# TreeShield.net
KiCad netlist of a schematic drawn in EAGLE
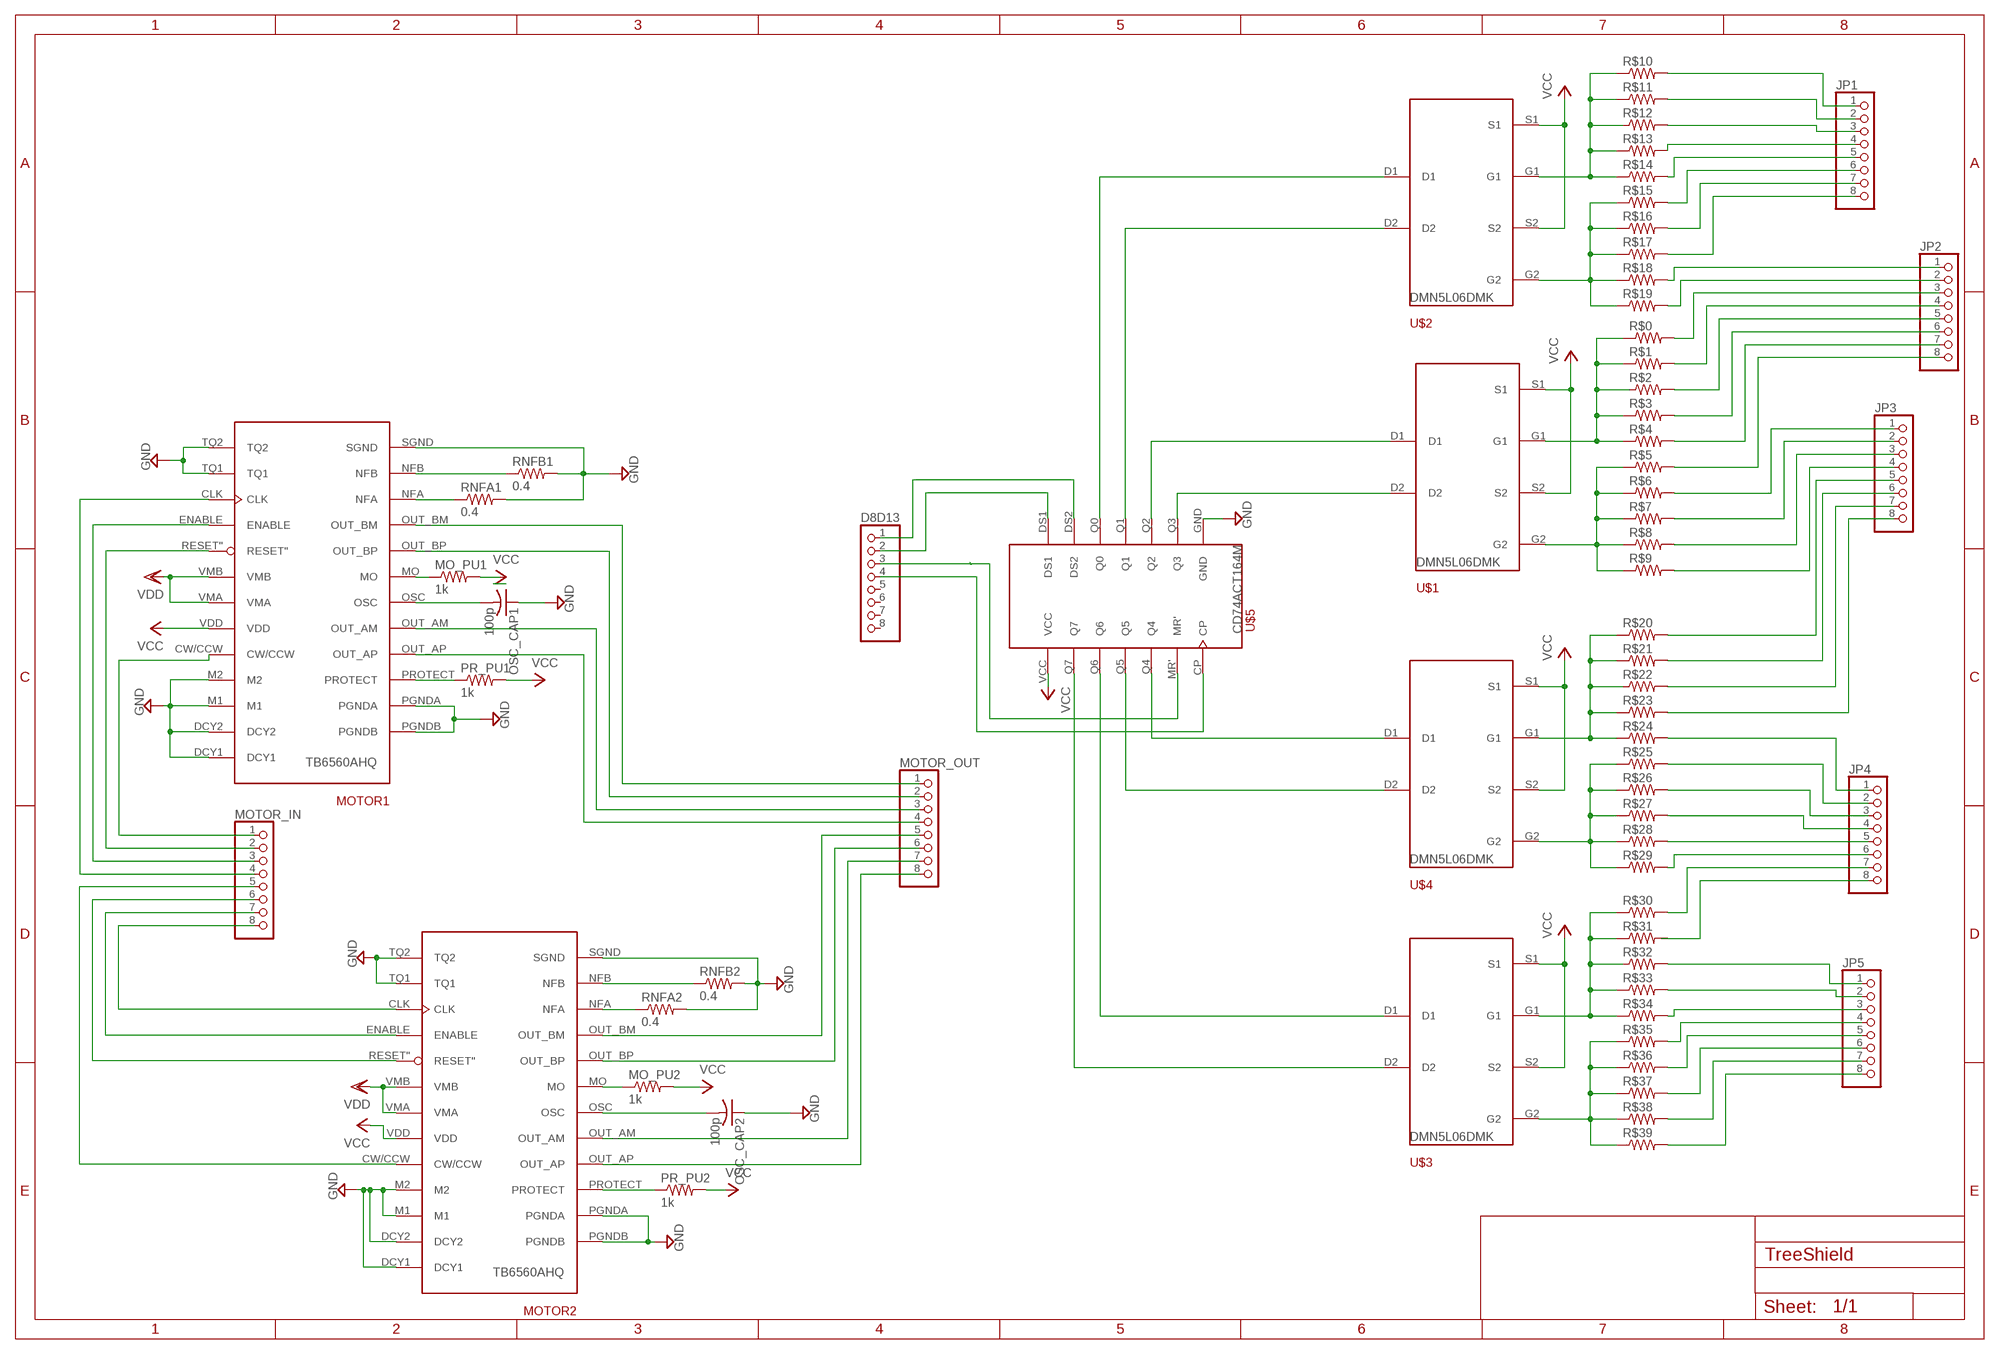
[diagram p0: schematic, sheet 1]

(export (version "E")
  (design (tool "Eeschema 10.0.6"))
  (components
    (comp (ref "D8D13")
      (value "PINHD-1X8CLEANBIG")
      (footprint "eagle-import:1X08-CLEANBIG")
      (libsource (lib "eagle-import") (part "PINHD-1X8CLEANBIG"))
    )
    (comp (ref "JP1")
      (value "PINHD-1X8BIG")
      (footprint "eagle-import:1X08-BIG")
      (libsource (lib "eagle-import") (part "PINHD-1X8BIG"))
    )
    (comp (ref "JP2")
      (value "PINHD-1X8BIG")
      (footprint "eagle-import:1X08-BIG")
      (libsource (lib "eagle-import") (part "PINHD-1X8BIG"))
    )
    (comp (ref "JP3")
      (value "PINHD-1X8BIG")
      (footprint "eagle-import:1X08-BIG")
      (libsource (lib "eagle-import") (part "PINHD-1X8BIG"))
    )
    (comp (ref "JP4")
      (value "PINHD-1X8BIG")
      (footprint "eagle-import:1X08-BIG")
      (libsource (lib "eagle-import") (part "PINHD-1X8BIG"))
    )
    (comp (ref "JP5")
      (value "PINHD-1X8BIG")
      (footprint "eagle-import:1X08-BIG")
      (libsource (lib "eagle-import") (part "PINHD-1X8BIG"))
    )
    (comp (ref "MOTOR1")
      (value "TB6560AHQ")
      (footprint "eagle-import:TB6560AHQ")
      (libsource (lib "eagle-import") (part "TB6560AHQ"))
    )
    (comp (ref "MOTOR2")
      (value "TB6560AHQ")
      (footprint "eagle-import:TB6560AHQ")
      (libsource (lib "eagle-import") (part "TB6560AHQ"))
    )
    (comp (ref "MOTOR_IN")
      (value "PINHD-1X8CLEANBIG")
      (footprint "eagle-import:1X08-CLEANBIG")
      (libsource (lib "eagle-import") (part "PINHD-1X8CLEANBIG"))
    )
    (comp (ref "MOTOR_OUT")
      (value "PINHD-1X8CLEANBIG")
      (footprint "eagle-import:1X08-CLEANBIG")
      (libsource (lib "eagle-import") (part "PINHD-1X8CLEANBIG"))
    )
    (comp (ref "MO_PU1")
      (value "1k")
      (footprint "eagle-import:R0603")
      (libsource (lib "eagle-import") (part "R-US_R0603"))
    )
    (comp (ref "MO_PU2")
      (value "1k")
      (footprint "eagle-import:R0603")
      (libsource (lib "eagle-import") (part "R-US_R0603"))
    )
    (comp (ref "OSC_CAP1")
      (value "100p")
      (footprint "eagle-import:C0603")
      (libsource (lib "eagle-import") (part "C-USC0603"))
    )
    (comp (ref "OSC_CAP2")
      (value "100p")
      (footprint "eagle-import:C0603")
      (libsource (lib "eagle-import") (part "C-USC0603"))
    )
    (comp (ref "PR_PU1")
      (value "1k")
      (footprint "eagle-import:R0603")
      (libsource (lib "eagle-import") (part "R-US_R0603"))
    )
    (comp (ref "PR_PU2")
      (value "1k")
      (footprint "eagle-import:R0603")
      (libsource (lib "eagle-import") (part "R-US_R0603"))
    )
    (comp (ref "R$0")
      (value "R-US_0817/7V")
      (footprint "eagle-import:P0817V")
      (libsource (lib "eagle-import") (part "resistor_R-US_0817/7V"))
    )
    (comp (ref "R$1")
      (value "R-US_0817/7V")
      (footprint "eagle-import:P0817V")
      (libsource (lib "eagle-import") (part "resistor_R-US_0817/7V"))
    )
    (comp (ref "R$2")
      (value "R-US_0817/7V")
      (footprint "eagle-import:P0817V")
      (libsource (lib "eagle-import") (part "resistor_R-US_0817/7V"))
    )
    (comp (ref "R$3")
      (value "R-US_0817/7V")
      (footprint "eagle-import:P0817V")
      (libsource (lib "eagle-import") (part "resistor_R-US_0817/7V"))
    )
    (comp (ref "R$4")
      (value "R-US_0817/7V")
      (footprint "eagle-import:P0817V")
      (libsource (lib "eagle-import") (part "resistor_R-US_0817/7V"))
    )
    (comp (ref "R$5")
      (value "R-US_0817/7V")
      (footprint "eagle-import:P0817V")
      (libsource (lib "eagle-import") (part "resistor_R-US_0817/7V"))
    )
    (comp (ref "R$6")
      (value "R-US_0817/7V")
      (footprint "eagle-import:P0817V")
      (libsource (lib "eagle-import") (part "resistor_R-US_0817/7V"))
    )
    (comp (ref "R$7")
      (value "R-US_0817/7V")
      (footprint "eagle-import:P0817V")
      (libsource (lib "eagle-import") (part "resistor_R-US_0817/7V"))
    )
    (comp (ref "R$8")
      (value "R-US_0817/7V")
      (footprint "eagle-import:P0817V")
      (libsource (lib "eagle-import") (part "resistor_R-US_0817/7V"))
    )
    (comp (ref "R$9")
      (value "R-US_0817/7V")
      (footprint "eagle-import:P0817V")
      (libsource (lib "eagle-import") (part "resistor_R-US_0817/7V"))
    )
    (comp (ref "R$10")
      (value "R-US_0817/7V")
      (footprint "eagle-import:P0817V")
      (libsource (lib "eagle-import") (part "resistor_R-US_0817/7V"))
    )
    (comp (ref "R$11")
      (value "R-US_0817/7V")
      (footprint "eagle-import:P0817V")
      (libsource (lib "eagle-import") (part "resistor_R-US_0817/7V"))
    )
    (comp (ref "R$12")
      (value "R-US_0817/7V")
      (footprint "eagle-import:P0817V")
      (libsource (lib "eagle-import") (part "resistor_R-US_0817/7V"))
    )
    (comp (ref "R$13")
      (value "R-US_0817/7V")
      (footprint "eagle-import:P0817V")
      (libsource (lib "eagle-import") (part "resistor_R-US_0817/7V"))
    )
    (comp (ref "R$14")
      (value "R-US_0817/7V")
      (footprint "eagle-import:P0817V")
      (libsource (lib "eagle-import") (part "resistor_R-US_0817/7V"))
    )
    (comp (ref "R$15")
      (value "R-US_0817/7V")
      (footprint "eagle-import:P0817V")
      (libsource (lib "eagle-import") (part "resistor_R-US_0817/7V"))
    )
    (comp (ref "R$16")
      (value "R-US_0817/7V")
      (footprint "eagle-import:P0817V")
      (libsource (lib "eagle-import") (part "resistor_R-US_0817/7V"))
    )
    (comp (ref "R$17")
      (value "R-US_0817/7V")
      (footprint "eagle-import:P0817V")
      (libsource (lib "eagle-import") (part "resistor_R-US_0817/7V"))
    )
    (comp (ref "R$18")
      (value "R-US_0817/7V")
      (footprint "eagle-import:P0817V")
      (libsource (lib "eagle-import") (part "resistor_R-US_0817/7V"))
    )
    (comp (ref "R$19")
      (value "R-US_0817/7V")
      (footprint "eagle-import:P0817V")
      (libsource (lib "eagle-import") (part "resistor_R-US_0817/7V"))
    )
    (comp (ref "R$20")
      (value "R-US_0817/7V")
      (footprint "eagle-import:P0817V")
      (libsource (lib "eagle-import") (part "resistor_R-US_0817/7V"))
    )
    (comp (ref "R$21")
      (value "R-US_0817/7V")
      (footprint "eagle-import:P0817V")
      (libsource (lib "eagle-import") (part "resistor_R-US_0817/7V"))
    )
    (comp (ref "R$22")
      (value "R-US_0817/7V")
      (footprint "eagle-import:P0817V")
      (libsource (lib "eagle-import") (part "resistor_R-US_0817/7V"))
    )
    (comp (ref "R$23")
      (value "R-US_0817/7V")
      (footprint "eagle-import:P0817V")
      (libsource (lib "eagle-import") (part "resistor_R-US_0817/7V"))
    )
    (comp (ref "R$24")
      (value "R-US_0817/7V")
      (footprint "eagle-import:P0817V")
      (libsource (lib "eagle-import") (part "resistor_R-US_0817/7V"))
    )
    (comp (ref "R$25")
      (value "R-US_0817/7V")
      (footprint "eagle-import:P0817V")
      (libsource (lib "eagle-import") (part "resistor_R-US_0817/7V"))
    )
    (comp (ref "R$26")
      (value "R-US_0817/7V")
      (footprint "eagle-import:P0817V")
      (libsource (lib "eagle-import") (part "resistor_R-US_0817/7V"))
    )
    (comp (ref "R$27")
      (value "R-US_0817/7V")
      (footprint "eagle-import:P0817V")
      (libsource (lib "eagle-import") (part "resistor_R-US_0817/7V"))
    )
    (comp (ref "R$28")
      (value "R-US_0817/7V")
      (footprint "eagle-import:P0817V")
      (libsource (lib "eagle-import") (part "resistor_R-US_0817/7V"))
    )
    (comp (ref "R$29")
      (value "R-US_0817/7V")
      (footprint "eagle-import:P0817V")
      (libsource (lib "eagle-import") (part "resistor_R-US_0817/7V"))
    )
    (comp (ref "R$30")
      (value "R-US_0817/7V")
      (footprint "eagle-import:P0817V")
      (libsource (lib "eagle-import") (part "resistor_R-US_0817/7V"))
    )
    (comp (ref "R$31")
      (value "R-US_0817/7V")
      (footprint "eagle-import:P0817V")
      (libsource (lib "eagle-import") (part "resistor_R-US_0817/7V"))
    )
    (comp (ref "R$32")
      (value "R-US_0817/7V")
      (footprint "eagle-import:P0817V")
      (libsource (lib "eagle-import") (part "resistor_R-US_0817/7V"))
    )
    (comp (ref "R$33")
      (value "R-US_0817/7V")
      (footprint "eagle-import:P0817V")
      (libsource (lib "eagle-import") (part "resistor_R-US_0817/7V"))
    )
    (comp (ref "R$34")
      (value "R-US_0817/7V")
      (footprint "eagle-import:P0817V")
      (libsource (lib "eagle-import") (part "resistor_R-US_0817/7V"))
    )
    (comp (ref "R$35")
      (value "R-US_0817/7V")
      (footprint "eagle-import:P0817V")
      (libsource (lib "eagle-import") (part "resistor_R-US_0817/7V"))
    )
    (comp (ref "R$36")
      (value "R-US_0817/7V")
      (footprint "eagle-import:P0817V")
      (libsource (lib "eagle-import") (part "resistor_R-US_0817/7V"))
    )
    (comp (ref "R$37")
      (value "R-US_0817/7V")
      (footprint "eagle-import:P0817V")
      (libsource (lib "eagle-import") (part "resistor_R-US_0817/7V"))
    )
    (comp (ref "R$38")
      (value "R-US_0817/7V")
      (footprint "eagle-import:P0817V")
      (libsource (lib "eagle-import") (part "resistor_R-US_0817/7V"))
    )
    (comp (ref "R$39")
      (value "R-US_0817/7V")
      (footprint "eagle-import:P0817V")
      (libsource (lib "eagle-import") (part "resistor_R-US_0817/7V"))
    )
    (comp (ref "RNFA1")
      (value "0.4")
      (footprint "eagle-import:P0817V")
      (libsource (lib "eagle-import") (part "resistor_R-US_0817/7V"))
    )
    (comp (ref "RNFA2")
      (value "0.4")
      (footprint "eagle-import:P0817V")
      (libsource (lib "eagle-import") (part "resistor_R-US_0817/7V"))
    )
    (comp (ref "RNFB1")
      (value "0.4")
      (footprint "eagle-import:P0817V")
      (libsource (lib "eagle-import") (part "resistor_R-US_0817/7V"))
    )
    (comp (ref "RNFB2")
      (value "0.4")
      (footprint "eagle-import:P0817V")
      (libsource (lib "eagle-import") (part "resistor_R-US_0817/7V"))
    )
    (comp (ref "U$1")
      (value "DMN5L06DMK")
      (footprint "eagle-import:DMN5L06DMK")
      (libsource (lib "eagle-import") (part "DMN5L06DMK"))
    )
    (comp (ref "U$2")
      (value "DMN5L06DMK")
      (footprint "eagle-import:DMN5L06DMK")
      (libsource (lib "eagle-import") (part "DMN5L06DMK"))
    )
    (comp (ref "U$3")
      (value "DMN5L06DMK")
      (footprint "eagle-import:DMN5L06DMK")
      (libsource (lib "eagle-import") (part "DMN5L06DMK"))
    )
    (comp (ref "U$4")
      (value "DMN5L06DMK")
      (footprint "eagle-import:DMN5L06DMK")
      (libsource (lib "eagle-import") (part "DMN5L06DMK"))
    )
    (comp (ref "U$5")
      (value "CD74ACT164M")
      (footprint "eagle-import:CD74ACT164M")
      (libsource (lib "eagle-import") (part "CD74ACT164M"))
    )
  )
  (nets
    (net (code "1") (name "GND") (class "Default")
      (node (ref "MOTOR1") (pin "DCY1") (pinfunction "DCY1_DCY1") (pintype "input"))
      (node (ref "MOTOR1") (pin "DCY2") (pinfunction "DCY2_DCY2") (pintype "input"))
      (node (ref "MOTOR1") (pin "M1") (pinfunction "M1_M1") (pintype "input"))
      (node (ref "MOTOR1") (pin "M2") (pinfunction "M2_M2") (pintype "input"))
      (node (ref "MOTOR1") (pin "PGNDA") (pinfunction "PGNDA_PGNDA") (pintype "bidirectional"))
      (node (ref "MOTOR1") (pin "PGNDB") (pinfunction "PGNDB_PGNDB") (pintype "bidirectional"))
      (node (ref "MOTOR1") (pin "SGND") (pinfunction "SGND_SGND") (pintype "bidirectional"))
      (node (ref "MOTOR1") (pin "TQ1") (pinfunction "TQ1_TQ1") (pintype "input"))
      (node (ref "MOTOR1") (pin "TQ2") (pinfunction "TQ2_TQ2") (pintype "input"))
      (node (ref "MOTOR2") (pin "DCY1") (pinfunction "DCY1_DCY1") (pintype "input"))
      (node (ref "MOTOR2") (pin "DCY2") (pinfunction "DCY2_DCY2") (pintype "input"))
      (node (ref "MOTOR2") (pin "M1") (pinfunction "M1_M1") (pintype "input"))
      (node (ref "MOTOR2") (pin "M2") (pinfunction "M2_M2") (pintype "input"))
      (node (ref "MOTOR2") (pin "PGNDA") (pinfunction "PGNDA_PGNDA") (pintype "bidirectional"))
      (node (ref "MOTOR2") (pin "PGNDB") (pinfunction "PGNDB_PGNDB") (pintype "bidirectional"))
      (node (ref "MOTOR2") (pin "SGND") (pinfunction "SGND_SGND") (pintype "bidirectional"))
      (node (ref "MOTOR2") (pin "TQ1") (pinfunction "TQ1_TQ1") (pintype "input"))
      (node (ref "MOTOR2") (pin "TQ2") (pinfunction "TQ2_TQ2") (pintype "input"))
      (node (ref "OSC_CAP1") (pin "1") (pinfunction "1_1") (pintype "passive"))
      (node (ref "OSC_CAP2") (pin "1") (pinfunction "1_1") (pintype "passive"))
      (node (ref "RNFA1") (pin "2") (pinfunction "2_2") (pintype "passive"))
      (node (ref "RNFA2") (pin "2") (pinfunction "2_2") (pintype "passive"))
      (node (ref "RNFB1") (pin "2") (pinfunction "2_2") (pintype "passive"))
      (node (ref "RNFB2") (pin "2") (pinfunction "2_2") (pintype "passive"))
      (node (ref "U$5") (pin "GND") (pinfunction "GND_GND") (pintype "bidirectional"))
    )
    (net (code "2") (name "Net-(D8D13-Pad1)") (class "Default")
      (node (ref "D8D13") (pin "1") (pinfunction "1_1") (pintype "passive"))
      (node (ref "U$5") (pin "DS2") (pinfunction "DS2_DS2") (pintype "bidirectional"))
    )
    (net (code "3") (name "Net-(D8D13-Pad2)") (class "Default")
      (node (ref "D8D13") (pin "2") (pinfunction "2_2") (pintype "passive"))
      (node (ref "U$5") (pin "DS1") (pinfunction "DS1_DS1") (pintype "bidirectional"))
    )
    (net (code "4") (name "Net-(D8D13-Pad3)") (class "Default")
      (node (ref "D8D13") (pin "3") (pinfunction "3_3") (pintype "passive"))
      (node (ref "U$5") (pin "MR'") (pinfunction "MR'_MR'") (pintype "bidirectional"))
    )
    (net (code "5") (name "Net-(D8D13-Pad4)") (class "Default")
      (node (ref "D8D13") (pin "4") (pinfunction "4_4") (pintype "passive"))
      (node (ref "U$5") (pin "CP") (pinfunction "CP_CP") (pintype "bidirectional"))
    )
    (net (code "6") (name "Net-(JP1-Pad1)") (class "Default")
      (node (ref "JP1") (pin "1") (pinfunction "1_1") (pintype "passive"))
      (node (ref "R$10") (pin "2") (pinfunction "2_2") (pintype "passive"))
    )
    (net (code "7") (name "Net-(JP1-Pad2)") (class "Default")
      (node (ref "JP1") (pin "2") (pinfunction "2_2") (pintype "passive"))
      (node (ref "R$11") (pin "2") (pinfunction "2_2") (pintype "passive"))
    )
    (net (code "8") (name "Net-(JP1-Pad3)") (class "Default")
      (node (ref "JP1") (pin "3") (pinfunction "3_3") (pintype "passive"))
      (node (ref "R$12") (pin "2") (pinfunction "2_2") (pintype "passive"))
    )
    (net (code "9") (name "Net-(JP1-Pad4)") (class "Default")
      (node (ref "JP1") (pin "4") (pinfunction "4_4") (pintype "passive"))
      (node (ref "R$13") (pin "2") (pinfunction "2_2") (pintype "passive"))
    )
    (net (code "10") (name "Net-(JP1-Pad5)") (class "Default")
      (node (ref "JP1") (pin "5") (pinfunction "5_5") (pintype "passive"))
      (node (ref "R$14") (pin "2") (pinfunction "2_2") (pintype "passive"))
    )
    (net (code "11") (name "Net-(JP1-Pad6)") (class "Default")
      (node (ref "JP1") (pin "6") (pinfunction "6_6") (pintype "passive"))
      (node (ref "R$15") (pin "2") (pinfunction "2_2") (pintype "passive"))
    )
    (net (code "12") (name "Net-(JP1-Pad7)") (class "Default")
      (node (ref "JP1") (pin "7") (pinfunction "7_7") (pintype "passive"))
      (node (ref "R$16") (pin "2") (pinfunction "2_2") (pintype "passive"))
    )
    (net (code "13") (name "Net-(JP1-Pad8)") (class "Default")
      (node (ref "JP1") (pin "8") (pinfunction "8_8") (pintype "passive"))
      (node (ref "R$17") (pin "2") (pinfunction "2_2") (pintype "passive"))
    )
    (net (code "14") (name "Net-(JP2-Pad1)") (class "Default")
      (node (ref "JP2") (pin "1") (pinfunction "1_1") (pintype "passive"))
      (node (ref "R$18") (pin "2") (pinfunction "2_2") (pintype "passive"))
    )
    (net (code "15") (name "Net-(JP2-Pad2)") (class "Default")
      (node (ref "JP2") (pin "2") (pinfunction "2_2") (pintype "passive"))
      (node (ref "R$19") (pin "2") (pinfunction "2_2") (pintype "passive"))
    )
    (net (code "16") (name "Net-(JP2-Pad3)") (class "Default")
      (node (ref "JP2") (pin "3") (pinfunction "3_3") (pintype "passive"))
      (node (ref "R$0") (pin "2") (pinfunction "2_2") (pintype "passive"))
    )
    (net (code "17") (name "Net-(JP2-Pad4)") (class "Default")
      (node (ref "JP2") (pin "4") (pinfunction "4_4") (pintype "passive"))
      (node (ref "R$1") (pin "2") (pinfunction "2_2") (pintype "passive"))
    )
    (net (code "18") (name "Net-(JP2-Pad5)") (class "Default")
      (node (ref "JP2") (pin "5") (pinfunction "5_5") (pintype "passive"))
      (node (ref "R$2") (pin "2") (pinfunction "2_2") (pintype "passive"))
    )
    (net (code "19") (name "Net-(JP2-Pad6)") (class "Default")
      (node (ref "JP2") (pin "6") (pinfunction "6_6") (pintype "passive"))
      (node (ref "R$3") (pin "2") (pinfunction "2_2") (pintype "passive"))
    )
    (net (code "20") (name "Net-(JP2-Pad7)") (class "Default")
      (node (ref "JP2") (pin "7") (pinfunction "7_7") (pintype "passive"))
      (node (ref "R$4") (pin "2") (pinfunction "2_2") (pintype "passive"))
    )
    (net (code "21") (name "Net-(JP2-Pad8)") (class "Default")
      (node (ref "JP2") (pin "8") (pinfunction "8_8") (pintype "passive"))
      (node (ref "R$5") (pin "2") (pinfunction "2_2") (pintype "passive"))
    )
    (net (code "22") (name "Net-(JP3-Pad1)") (class "Default")
      (node (ref "JP3") (pin "1") (pinfunction "1_1") (pintype "passive"))
      (node (ref "R$6") (pin "2") (pinfunction "2_2") (pintype "passive"))
    )
    (net (code "23") (name "Net-(JP3-Pad2)") (class "Default")
      (node (ref "JP3") (pin "2") (pinfunction "2_2") (pintype "passive"))
      (node (ref "R$7") (pin "2") (pinfunction "2_2") (pintype "passive"))
    )
    (net (code "24") (name "Net-(JP3-Pad3)") (class "Default")
      (node (ref "JP3") (pin "3") (pinfunction "3_3") (pintype "passive"))
      (node (ref "R$8") (pin "2") (pinfunction "2_2") (pintype "passive"))
    )
    (net (code "25") (name "Net-(JP3-Pad4)") (class "Default")
      (node (ref "JP3") (pin "4") (pinfunction "4_4") (pintype "passive"))
      (node (ref "R$9") (pin "2") (pinfunction "2_2") (pintype "passive"))
    )
    (net (code "26") (name "Net-(JP3-Pad5)") (class "Default")
      (node (ref "JP3") (pin "5") (pinfunction "5_5") (pintype "passive"))
      (node (ref "R$20") (pin "2") (pinfunction "2_2") (pintype "passive"))
    )
    (net (code "27") (name "Net-(JP3-Pad6)") (class "Default")
      (node (ref "JP3") (pin "6") (pinfunction "6_6") (pintype "passive"))
      (node (ref "R$21") (pin "2") (pinfunction "2_2") (pintype "passive"))
    )
    (net (code "28") (name "Net-(JP3-Pad7)") (class "Default")
      (node (ref "JP3") (pin "7") (pinfunction "7_7") (pintype "passive"))
      (node (ref "R$22") (pin "2") (pinfunction "2_2") (pintype "passive"))
    )
    (net (code "29") (name "Net-(JP3-Pad8)") (class "Default")
      (node (ref "JP3") (pin "8") (pinfunction "8_8") (pintype "passive"))
      (node (ref "R$23") (pin "2") (pinfunction "2_2") (pintype "passive"))
    )
    (net (code "30") (name "Net-(JP4-Pad1)") (class "Default")
      (node (ref "JP4") (pin "1") (pinfunction "1_1") (pintype "passive"))
      (node (ref "R$24") (pin "2") (pinfunction "2_2") (pintype "passive"))
    )
    (net (code "31") (name "Net-(JP4-Pad2)") (class "Default")
      (node (ref "JP4") (pin "2") (pinfunction "2_2") (pintype "passive"))
      (node (ref "R$25") (pin "2") (pinfunction "2_2") (pintype "passive"))
    )
    (net (code "32") (name "Net-(JP4-Pad3)") (class "Default")
      (node (ref "JP4") (pin "3") (pinfunction "3_3") (pintype "passive"))
      (node (ref "R$26") (pin "2") (pinfunction "2_2") (pintype "passive"))
    )
    (net (code "33") (name "Net-(JP4-Pad4)") (class "Default")
      (node (ref "JP4") (pin "4") (pinfunction "4_4") (pintype "passive"))
      (node (ref "R$27") (pin "2") (pinfunction "2_2") (pintype "passive"))
    )
    (net (code "34") (name "Net-(JP4-Pad5)") (class "Default")
      (node (ref "JP4") (pin "5") (pinfunction "5_5") (pintype "passive"))
      (node (ref "R$28") (pin "2") (pinfunction "2_2") (pintype "passive"))
    )
    (net (code "35") (name "Net-(JP4-Pad6)") (class "Default")
      (node (ref "JP4") (pin "6") (pinfunction "6_6") (pintype "passive"))
      (node (ref "R$29") (pin "2") (pinfunction "2_2") (pintype "passive"))
    )
    (net (code "36") (name "Net-(JP4-Pad7)") (class "Default")
      (node (ref "JP4") (pin "7") (pinfunction "7_7") (pintype "passive"))
      (node (ref "R$30") (pin "2") (pinfunction "2_2") (pintype "passive"))
    )
    (net (code "37") (name "Net-(JP5-Pad1)") (class "Default")
      (node (ref "JP5") (pin "1") (pinfunction "1_1") (pintype "passive"))
      (node (ref "R$32") (pin "2") (pinfunction "2_2") (pintype "passive"))
    )
    (net (code "38") (name "Net-(JP5-Pad2)") (class "Default")
      (node (ref "JP5") (pin "2") (pinfunction "2_2") (pintype "passive"))
      (node (ref "R$33") (pin "2") (pinfunction "2_2") (pintype "passive"))
    )
    (net (code "39") (name "Net-(JP5-Pad3)") (class "Default")
      (node (ref "JP5") (pin "3") (pinfunction "3_3") (pintype "passive"))
      (node (ref "R$34") (pin "2") (pinfunction "2_2") (pintype "passive"))
    )
    (net (code "40") (name "Net-(JP5-Pad4)") (class "Default")
      (node (ref "JP5") (pin "4") (pinfunction "4_4") (pintype "passive"))
      (node (ref "R$35") (pin "2") (pinfunction "2_2") (pintype "passive"))
    )
    (net (code "41") (name "Net-(JP5-Pad5)") (class "Default")
      (node (ref "JP5") (pin "5") (pinfunction "5_5") (pintype "passive"))
      (node (ref "R$36") (pin "2") (pinfunction "2_2") (pintype "passive"))
    )
    (net (code "42") (name "Net-(JP5-Pad6)") (class "Default")
      (node (ref "JP5") (pin "6") (pinfunction "6_6") (pintype "passive"))
      (node (ref "R$37") (pin "2") (pinfunction "2_2") (pintype "passive"))
    )
    (net (code "43") (name "Net-(JP5-Pad7)") (class "Default")
      (node (ref "JP5") (pin "7") (pinfunction "7_7") (pintype "passive"))
      (node (ref "R$38") (pin "2") (pinfunction "2_2") (pintype "passive"))
    )
    (net (code "44") (name "Net-(JP5-Pad8)") (class "Default")
      (node (ref "JP5") (pin "8") (pinfunction "8_8") (pintype "passive"))
      (node (ref "R$39") (pin "2") (pinfunction "2_2") (pintype "passive"))
    )
    (net (code "45") (name "Net-(MOTOR1-PadCLK)") (class "Default")
      (node (ref "MOTOR1") (pin "CLK") (pinfunction "CLK_CLK") (pintype "input"))
      (node (ref "MOTOR_IN") (pin "4") (pinfunction "4_4") (pintype "passive"))
    )
    (net (code "46") (name "Net-(MOTOR1-PadCW{slash}CCW)") (class "Default")
      (node (ref "MOTOR1") (pin "CW/CCW") (pinfunction "CW/CCW_CW/CCW") (pintype "input"))
      (node (ref "MOTOR_IN") (pin "1") (pinfunction "1_1") (pintype "passive"))
    )
    (net (code "47") (name "Net-(MOTOR1-PadENABLE)") (class "Default")
      (node (ref "MOTOR1") (pin "ENABLE") (pinfunction "ENABLE_ENABLE") (pintype "input"))
      (node (ref "MOTOR_IN") (pin "3") (pinfunction "3_3") (pintype "passive"))
    )
    (net (code "48") (name "Net-(MOTOR1-PadMO)") (class "Default")
      (node (ref "MOTOR1") (pin "MO") (pinfunction "MO_MO") (pintype "output"))
      (node (ref "MO_PU1") (pin "1") (pinfunction "1_1") (pintype "passive"))
    )
    (net (code "49") (name "Net-(MOTOR1-PadNFA)") (class "Default")
      (node (ref "MOTOR1") (pin "NFA") (pinfunction "NFA_NFA") (pintype "bidirectional"))
      (node (ref "RNFA1") (pin "1") (pinfunction "1_1") (pintype "passive"))
    )
    (net (code "50") (name "Net-(MOTOR1-PadNFB)") (class "Default")
      (node (ref "MOTOR1") (pin "NFB") (pinfunction "NFB_NFB") (pintype "bidirectional"))
      (node (ref "RNFB1") (pin "1") (pinfunction "1_1") (pintype "passive"))
    )
    (net (code "51") (name "Net-(MOTOR1-PadOSC)") (class "Default")
      (node (ref "MOTOR1") (pin "OSC") (pinfunction "OSC_OSC") (pintype "bidirectional"))
      (node (ref "OSC_CAP1") (pin "2") (pinfunction "2_2") (pintype "passive"))
    )
    (net (code "52") (name "Net-(MOTOR1-PadOUT_AM)") (class "Default")
      (node (ref "MOTOR1") (pin "OUT_AM") (pinfunction "OUT_AM_OUT_AM") (pintype "output"))
      (node (ref "MOTOR_OUT") (pin "3") (pinfunction "3_3") (pintype "passive"))
    )
    (net (code "53") (name "Net-(MOTOR1-PadOUT_AP)") (class "Default")
      (node (ref "MOTOR1") (pin "OUT_AP") (pinfunction "OUT_AP_OUT_AP") (pintype "output"))
      (node (ref "MOTOR_OUT") (pin "4") (pinfunction "4_4") (pintype "passive"))
    )
    (net (code "54") (name "Net-(MOTOR1-PadOUT_BM)") (class "Default")
      (node (ref "MOTOR1") (pin "OUT_BM") (pinfunction "OUT_BM_OUT_BM") (pintype "output"))
      (node (ref "MOTOR_OUT") (pin "1") (pinfunction "1_1") (pintype "passive"))
    )
    (net (code "55") (name "Net-(MOTOR1-PadOUT_BP)") (class "Default")
      (node (ref "MOTOR1") (pin "OUT_BP") (pinfunction "OUT_BP_OUT_BP") (pintype "output"))
      (node (ref "MOTOR_OUT") (pin "2") (pinfunction "2_2") (pintype "passive"))
    )
    (net (code "56") (name "Net-(MOTOR1-PadPROTECT)") (class "Default")
      (node (ref "MOTOR1") (pin "PROTECT") (pinfunction "PROTECT_PROTECT") (pintype "output"))
      (node (ref "PR_PU1") (pin "1") (pinfunction "1_1") (pintype "passive"))
    )
    (net (code "57") (name "Net-(MOTOR1-PadRESET'')") (class "Default")
      (node (ref "MOTOR1") (pin "RESET''") (pinfunction "RESET''_RESET''") (pintype "input"))
      (node (ref "MOTOR_IN") (pin "2") (pinfunction "2_2") (pintype "passive"))
    )
    (net (code "58") (name "Net-(MOTOR2-PadCLK)") (class "Default")
      (node (ref "MOTOR2") (pin "CLK") (pinfunction "CLK_CLK") (pintype "input"))
      (node (ref "MOTOR_IN") (pin "8") (pinfunction "8_8") (pintype "passive"))
    )
    (net (code "59") (name "Net-(MOTOR2-PadCW{slash}CCW)") (class "Default")
      (node (ref "MOTOR2") (pin "CW/CCW") (pinfunction "CW/CCW_CW/CCW") (pintype "input"))
      (node (ref "MOTOR_IN") (pin "5") (pinfunction "5_5") (pintype "passive"))
    )
    (net (code "60") (name "Net-(MOTOR2-PadENABLE)") (class "Default")
      (node (ref "MOTOR2") (pin "ENABLE") (pinfunction "ENABLE_ENABLE") (pintype "input"))
      (node (ref "MOTOR_IN") (pin "7") (pinfunction "7_7") (pintype "passive"))
    )
    (net (code "61") (name "Net-(MOTOR2-PadMO)") (class "Default")
      (node (ref "MOTOR2") (pin "MO") (pinfunction "MO_MO") (pintype "output"))
      (node (ref "MO_PU2") (pin "1") (pinfunction "1_1") (pintype "passive"))
    )
    (net (code "62") (name "Net-(MOTOR2-PadNFA)") (class "Default")
      (node (ref "MOTOR2") (pin "NFA") (pinfunction "NFA_NFA") (pintype "bidirectional"))
      (node (ref "RNFA2") (pin "1") (pinfunction "1_1") (pintype "passive"))
    )
    (net (code "63") (name "Net-(MOTOR2-PadNFB)") (class "Default")
      (node (ref "MOTOR2") (pin "NFB") (pinfunction "NFB_NFB") (pintype "bidirectional"))
      (node (ref "RNFB2") (pin "1") (pinfunction "1_1") (pintype "passive"))
    )
    (net (code "64") (name "Net-(MOTOR2-PadOSC)") (class "Default")
      (node (ref "MOTOR2") (pin "OSC") (pinfunction "OSC_OSC") (pintype "bidirectional"))
      (node (ref "OSC_CAP2") (pin "2") (pinfunction "2_2") (pintype "passive"))
    )
    (net (code "65") (name "Net-(MOTOR2-PadOUT_AM)") (class "Default")
      (node (ref "MOTOR2") (pin "OUT_AM") (pinfunction "OUT_AM_OUT_AM") (pintype "output"))
      (node (ref "MOTOR_OUT") (pin "7") (pinfunction "7_7") (pintype "passive"))
    )
    (net (code "66") (name "Net-(MOTOR2-PadOUT_AP)") (class "Default")
      (node (ref "MOTOR2") (pin "OUT_AP") (pinfunction "OUT_AP_OUT_AP") (pintype "output"))
      (node (ref "MOTOR_OUT") (pin "8") (pinfunction "8_8") (pintype "passive"))
    )
    (net (code "67") (name "Net-(MOTOR2-PadOUT_BM)") (class "Default")
      (node (ref "MOTOR2") (pin "OUT_BM") (pinfunction "OUT_BM_OUT_BM") (pintype "output"))
      (node (ref "MOTOR_OUT") (pin "5") (pinfunction "5_5") (pintype "passive"))
    )
    (net (code "68") (name "Net-(MOTOR2-PadOUT_BP)") (class "Default")
      (node (ref "MOTOR2") (pin "OUT_BP") (pinfunction "OUT_BP_OUT_BP") (pintype "output"))
      (node (ref "MOTOR_OUT") (pin "6") (pinfunction "6_6") (pintype "passive"))
    )
    (net (code "69") (name "Net-(MOTOR2-PadPROTECT)") (class "Default")
      (node (ref "MOTOR2") (pin "PROTECT") (pinfunction "PROTECT_PROTECT") (pintype "output"))
      (node (ref "PR_PU2") (pin "1") (pinfunction "1_1") (pintype "passive"))
    )
    (net (code "70") (name "Net-(MOTOR2-PadRESET'')") (class "Default")
      (node (ref "MOTOR2") (pin "RESET''") (pinfunction "RESET''_RESET''") (pintype "input"))
      (node (ref "MOTOR_IN") (pin "6") (pinfunction "6_6") (pintype "passive"))
    )
    (net (code "71") (name "Net-(R$0-Pad1)") (class "Default")
      (node (ref "R$0") (pin "1") (pinfunction "1_1") (pintype "passive"))
      (node (ref "R$1") (pin "1") (pinfunction "1_1") (pintype "passive"))
      (node (ref "R$3") (pin "1") (pinfunction "1_1") (pintype "passive"))
      (node (ref "R$4") (pin "1") (pinfunction "1_1") (pintype "passive"))
      (node (ref "U$1") (pin "G1") (pinfunction "G1_G1") (pintype "input"))
    )
    (net (code "72") (name "Net-(R$5-Pad1)") (class "Default")
      (node (ref "R$5") (pin "1") (pinfunction "1_1") (pintype "passive"))
      (node (ref "R$6") (pin "1") (pinfunction "1_1") (pintype "passive"))
      (node (ref "R$7") (pin "1") (pinfunction "1_1") (pintype "passive"))
      (node (ref "R$8") (pin "1") (pinfunction "1_1") (pintype "passive"))
      (node (ref "R$9") (pin "1") (pinfunction "1_1") (pintype "passive"))
      (node (ref "U$1") (pin "G2") (pinfunction "G2_G2") (pintype "input"))
    )
    (net (code "73") (name "Net-(R$10-Pad1)") (class "Default")
      (node (ref "R$10") (pin "1") (pinfunction "1_1") (pintype "passive"))
      (node (ref "R$11") (pin "1") (pinfunction "1_1") (pintype "passive"))
      (node (ref "R$13") (pin "1") (pinfunction "1_1") (pintype "passive"))
      (node (ref "R$14") (pin "1") (pinfunction "1_1") (pintype "passive"))
      (node (ref "U$2") (pin "G1") (pinfunction "G1_G1") (pintype "input"))
    )
    (net (code "74") (name "Net-(R$15-Pad1)") (class "Default")
      (node (ref "R$15") (pin "1") (pinfunction "1_1") (pintype "passive"))
      (node (ref "R$16") (pin "1") (pinfunction "1_1") (pintype "passive"))
      (node (ref "R$17") (pin "1") (pinfunction "1_1") (pintype "passive"))
      (node (ref "R$18") (pin "1") (pinfunction "1_1") (pintype "passive"))
      (node (ref "R$19") (pin "1") (pinfunction "1_1") (pintype "passive"))
      (node (ref "U$2") (pin "G2") (pinfunction "G2_G2") (pintype "input"))
    )
    (net (code "75") (name "Net-(R$20-Pad1)") (class "Default")
      (node (ref "R$20") (pin "1") (pinfunction "1_1") (pintype "passive"))
      (node (ref "R$21") (pin "1") (pinfunction "1_1") (pintype "passive"))
      (node (ref "R$23") (pin "1") (pinfunction "1_1") (pintype "passive"))
      (node (ref "R$24") (pin "1") (pinfunction "1_1") (pintype "passive"))
      (node (ref "U$4") (pin "G1") (pinfunction "G1_G1") (pintype "input"))
    )
    (net (code "76") (name "Net-(R$25-Pad1)") (class "Default")
      (node (ref "R$25") (pin "1") (pinfunction "1_1") (pintype "passive"))
      (node (ref "R$26") (pin "1") (pinfunction "1_1") (pintype "passive"))
      (node (ref "R$27") (pin "1") (pinfunction "1_1") (pintype "passive"))
      (node (ref "R$28") (pin "1") (pinfunction "1_1") (pintype "passive"))
      (node (ref "R$29") (pin "1") (pinfunction "1_1") (pintype "passive"))
      (node (ref "U$4") (pin "G2") (pinfunction "G2_G2") (pintype "input"))
    )
    (net (code "77") (name "Net-(R$30-Pad1)") (class "Default")
      (node (ref "R$30") (pin "1") (pinfunction "1_1") (pintype "passive"))
      (node (ref "R$31") (pin "1") (pinfunction "1_1") (pintype "passive"))
      (node (ref "R$33") (pin "1") (pinfunction "1_1") (pintype "passive"))
      (node (ref "R$34") (pin "1") (pinfunction "1_1") (pintype "passive"))
      (node (ref "U$3") (pin "G1") (pinfunction "G1_G1") (pintype "input"))
    )
    (net (code "78") (name "Net-(R$35-Pad1)") (class "Default")
      (node (ref "R$35") (pin "1") (pinfunction "1_1") (pintype "passive"))
      (node (ref "R$36") (pin "1") (pinfunction "1_1") (pintype "passive"))
      (node (ref "R$37") (pin "1") (pinfunction "1_1") (pintype "passive"))
      (node (ref "R$38") (pin "1") (pinfunction "1_1") (pintype "passive"))
      (node (ref "R$39") (pin "1") (pinfunction "1_1") (pintype "passive"))
      (node (ref "U$3") (pin "G2") (pinfunction "G2_G2") (pintype "input"))
    )
    (net (code "79") (name "Net-(U$1-PadD1)") (class "Default")
      (node (ref "U$1") (pin "D1") (pinfunction "D1_D1") (pintype "output"))
      (node (ref "U$5") (pin "Q2") (pinfunction "Q2_Q2") (pintype "bidirectional"))
    )
    (net (code "80") (name "Net-(U$1-PadD2)") (class "Default")
      (node (ref "U$1") (pin "D2") (pinfunction "D2_D2") (pintype "output"))
      (node (ref "U$5") (pin "Q3") (pinfunction "Q3_Q3") (pintype "bidirectional"))
    )
    (net (code "81") (name "Net-(U$2-PadD1)") (class "Default")
      (node (ref "U$2") (pin "D1") (pinfunction "D1_D1") (pintype "output"))
      (node (ref "U$5") (pin "Q0") (pinfunction "Q0_Q0") (pintype "bidirectional"))
    )
    (net (code "82") (name "Net-(U$2-PadD2)") (class "Default")
      (node (ref "U$2") (pin "D2") (pinfunction "D2_D2") (pintype "output"))
      (node (ref "U$5") (pin "Q1") (pinfunction "Q1_Q1") (pintype "bidirectional"))
    )
    (net (code "83") (name "Net-(U$3-PadD1)") (class "Default")
      (node (ref "U$3") (pin "D1") (pinfunction "D1_D1") (pintype "output"))
      (node (ref "U$5") (pin "Q6") (pinfunction "Q6_Q6") (pintype "bidirectional"))
    )
    (net (code "84") (name "Net-(U$3-PadD2)") (class "Default")
      (node (ref "U$3") (pin "D2") (pinfunction "D2_D2") (pintype "output"))
      (node (ref "U$5") (pin "Q7") (pinfunction "Q7_Q7") (pintype "bidirectional"))
    )
    (net (code "85") (name "Net-(U$4-PadD1)") (class "Default")
      (node (ref "U$4") (pin "D1") (pinfunction "D1_D1") (pintype "output"))
      (node (ref "U$5") (pin "Q4") (pinfunction "Q4_Q4") (pintype "bidirectional"))
    )
    (net (code "86") (name "Net-(U$4-PadD2)") (class "Default")
      (node (ref "U$4") (pin "D2") (pinfunction "D2_D2") (pintype "output"))
      (node (ref "U$5") (pin "Q5") (pinfunction "Q5_Q5") (pintype "bidirectional"))
    )
    (net (code "87") (name "VCC") (class "Default")
      (node (ref "MOTOR1") (pin "VDD") (pinfunction "VDD_VDD") (pintype "input"))
      (node (ref "MOTOR2") (pin "VDD") (pinfunction "VDD_VDD") (pintype "input"))
      (node (ref "MO_PU1") (pin "2") (pinfunction "2_2") (pintype "passive"))
      (node (ref "MO_PU2") (pin "2") (pinfunction "2_2") (pintype "passive"))
      (node (ref "PR_PU1") (pin "2") (pinfunction "2_2") (pintype "passive"))
      (node (ref "PR_PU2") (pin "2") (pinfunction "2_2") (pintype "passive"))
      (node (ref "U$1") (pin "S1") (pinfunction "S1_S1") (pintype "input"))
      (node (ref "U$1") (pin "S2") (pinfunction "S2_S2") (pintype "input"))
      (node (ref "U$2") (pin "S1") (pinfunction "S1_S1") (pintype "input"))
      (node (ref "U$2") (pin "S2") (pinfunction "S2_S2") (pintype "input"))
      (node (ref "U$3") (pin "S1") (pinfunction "S1_S1") (pintype "input"))
      (node (ref "U$3") (pin "S2") (pinfunction "S2_S2") (pintype "input"))
      (node (ref "U$4") (pin "S1") (pinfunction "S1_S1") (pintype "input"))
      (node (ref "U$4") (pin "S2") (pinfunction "S2_S2") (pintype "input"))
      (node (ref "U$5") (pin "VCC") (pinfunction "VCC_VCC") (pintype "bidirectional"))
    )
    (net (code "88") (name "VDD") (class "Default")
      (node (ref "MOTOR1") (pin "VMA") (pinfunction "VMA_VMA") (pintype "input"))
      (node (ref "MOTOR1") (pin "VMB") (pinfunction "VMB_VMB") (pintype "input"))
      (node (ref "MOTOR2") (pin "VMA") (pinfunction "VMA_VMA") (pintype "input"))
      (node (ref "MOTOR2") (pin "VMB") (pinfunction "VMB_VMB") (pintype "input"))
    )
    (net (code "89") (name "unconnected-(D8D13-Pad5)") (class "Default")
      (node (ref "D8D13") (pin "5") (pinfunction "5_5") (pintype "passive"))
    )
    (net (code "90") (name "unconnected-(D8D13-Pad6)") (class "Default")
      (node (ref "D8D13") (pin "6") (pinfunction "6_6") (pintype "passive"))
    )
    (net (code "91") (name "unconnected-(D8D13-Pad7)") (class "Default")
      (node (ref "D8D13") (pin "7") (pinfunction "7_7") (pintype "passive"))
    )
    (net (code "92") (name "unconnected-(D8D13-Pad8)") (class "Default")
      (node (ref "D8D13") (pin "8") (pinfunction "8_8") (pintype "passive"))
    )
    (net (code "93") (name "unconnected-(JP4-Pad8)") (class "Default")
      (node (ref "JP4") (pin "8") (pinfunction "8_8") (pintype "passive"))
    )
    (net (code "94") (name "unconnected-(R$2-Pad1)") (class "Default")
      (node (ref "R$2") (pin "1") (pinfunction "1_1") (pintype "passive"))
    )
    (net (code "95") (name "unconnected-(R$12-Pad1)") (class "Default")
      (node (ref "R$12") (pin "1") (pinfunction "1_1") (pintype "passive"))
    )
    (net (code "96") (name "unconnected-(R$22-Pad1)") (class "Default")
      (node (ref "R$22") (pin "1") (pinfunction "1_1") (pintype "passive"))
    )
    (net (code "97") (name "unconnected-(R$31-Pad2)") (class "Default")
      (node (ref "R$31") (pin "2") (pinfunction "2_2") (pintype "passive"))
    )
    (net (code "98") (name "unconnected-(R$32-Pad1)") (class "Default")
      (node (ref "R$32") (pin "1") (pinfunction "1_1") (pintype "passive"))
    )
  )
)
